# placa_nano.net
KiCad netlist of a schematic drawn in EAGLE
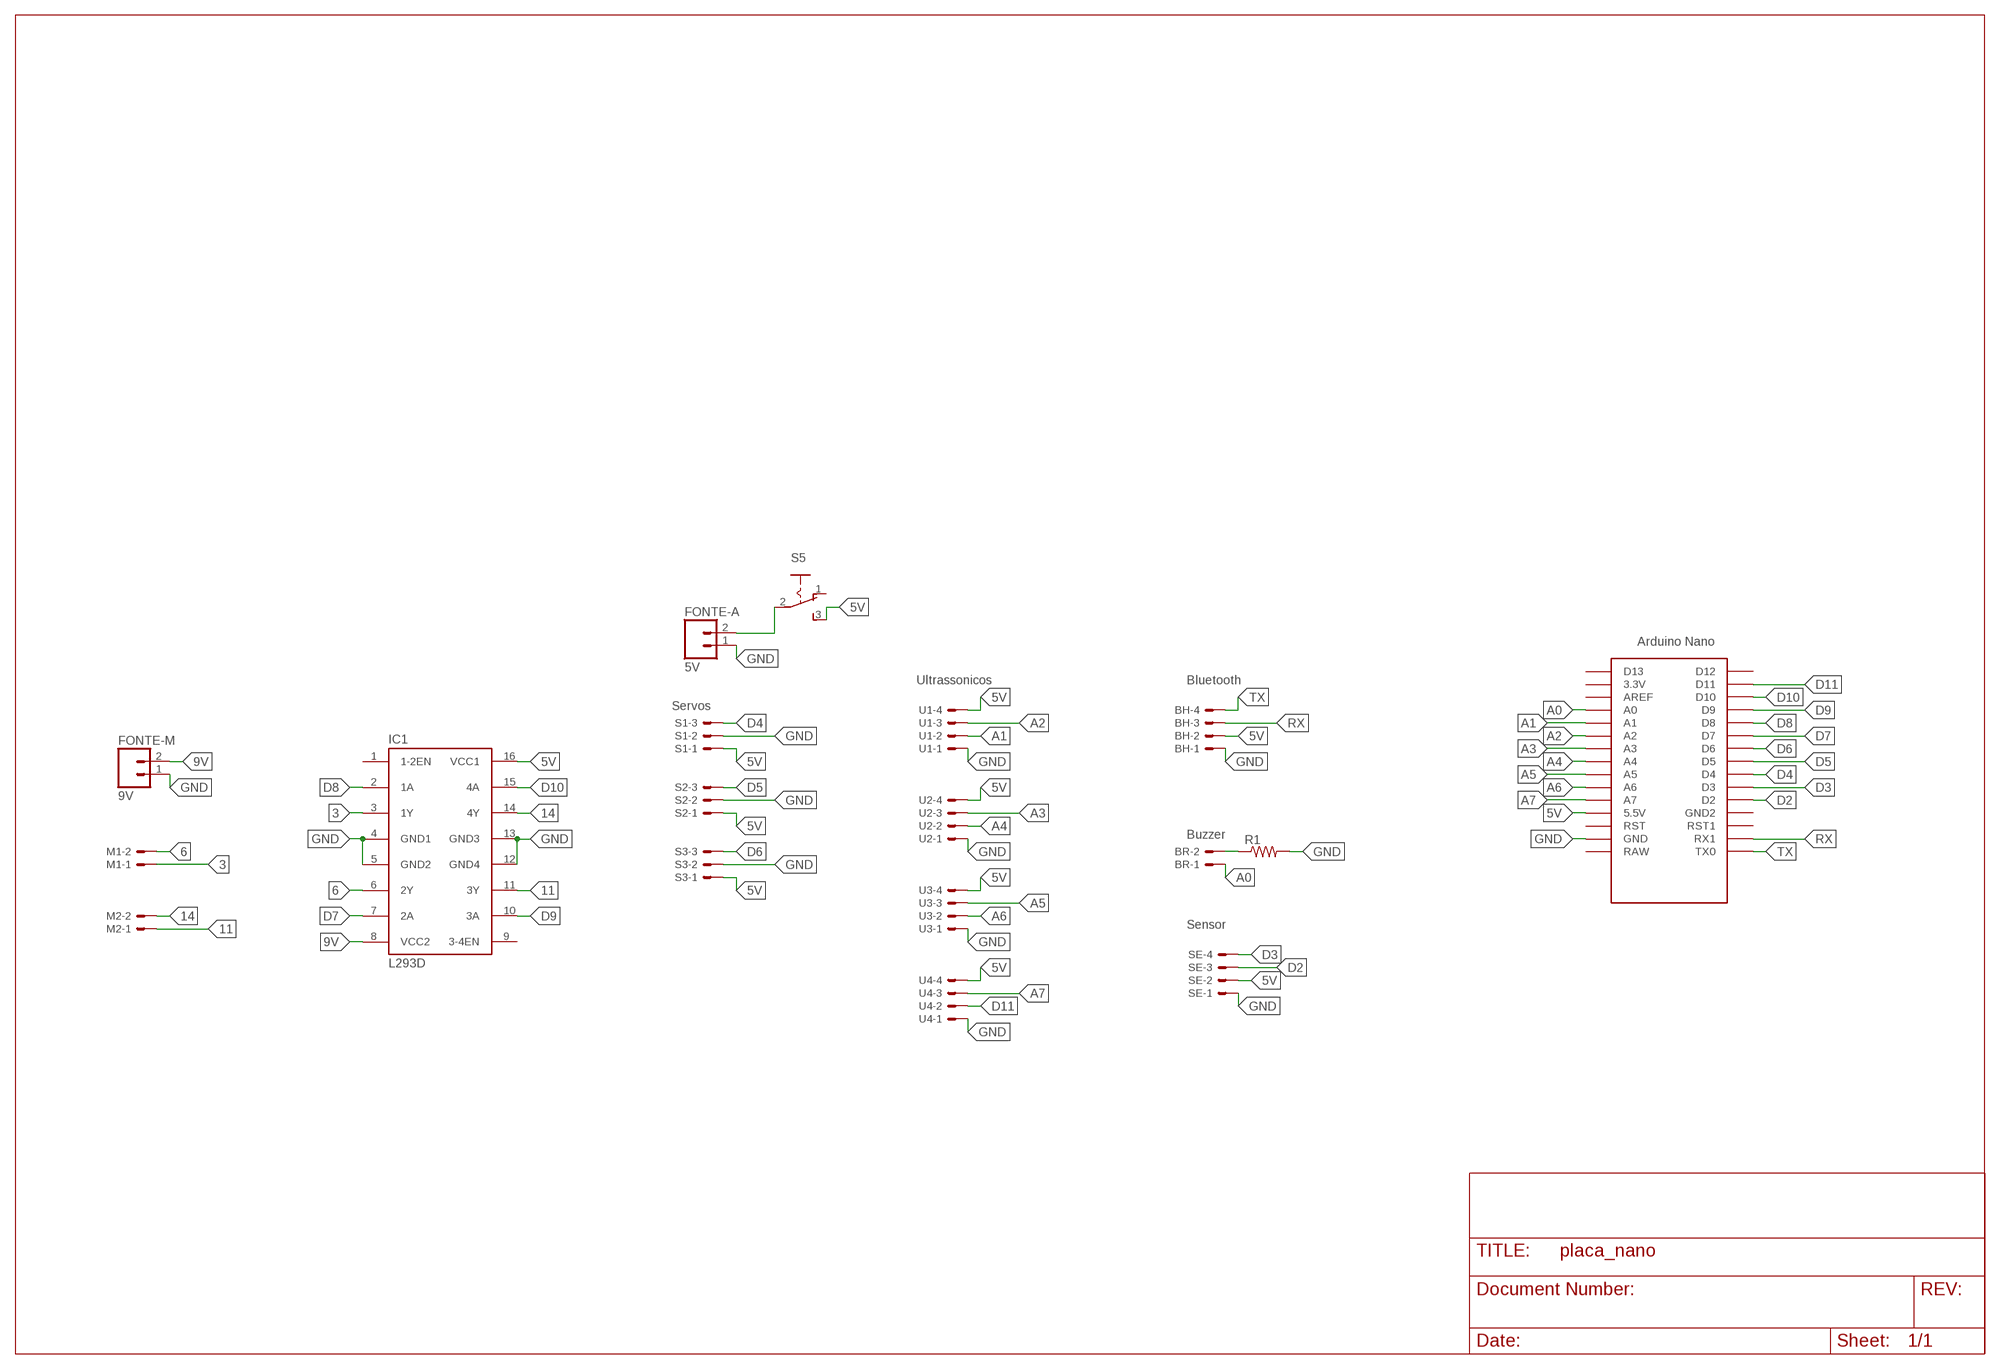
[diagram p0: schematic, sheet 1]

(export (version "E")
  (design (tool "Eeschema 10.0.6"))
  (components
    (comp (ref "BH")
      (value "22-23-2041")
      (footprint "eagle-import:22-23-2041")
      (fields (field (name "MF") "MOLEX"))
      (libsource (lib "eagle-import") (part "22-23-2041"))
    )
    (comp (ref "BR")
      (value "22-23-2021")
      (footprint "eagle-import:22-23-2021")
      (fields (field (name "MF") "MOLEX"))
      (libsource (lib "eagle-import") (part "22-23-2021"))
    )
    (comp (ref "FONTE-A")
      (value "5V")
      (footprint "eagle-import:02P")
      (libsource (lib "eagle-import") (part "M02"))
    )
    (comp (ref "FONTE-M")
      (value "9V")
      (footprint "eagle-import:02P")
      (libsource (lib "eagle-import") (part "M02"))
    )
    (comp (ref "IC1")
      (value "L293D")
      (footprint "eagle-import:DIL16")
      (libsource (lib "eagle-import") (part "L293D"))
    )
    (comp (ref "M1")
      (value "22-23-2021")
      (footprint "eagle-import:22-23-2021")
      (fields (field (name "MF") "MOLEX"))
      (libsource (lib "eagle-import") (part "22-23-2021"))
    )
    (comp (ref "M2")
      (value "22-23-2021")
      (footprint "eagle-import:22-23-2021")
      (fields (field (name "MF") "MOLEX"))
      (libsource (lib "eagle-import") (part "22-23-2021"))
    )
    (comp (ref "R1")
      (value "R-US_0207/10")
      (footprint "eagle-import:0207_10")
      (libsource (lib "eagle-import") (part "R-US_0207/10"))
    )
    (comp (ref "S1")
      (value "22-23-2031")
      (footprint "eagle-import:22-23-2031")
      (fields (field (name "MF") "MOLEX"))
      (libsource (lib "eagle-import") (part "22-23-2031"))
    )
    (comp (ref "S2")
      (value "22-23-2031")
      (footprint "eagle-import:22-23-2031")
      (fields (field (name "MF") "MOLEX"))
      (libsource (lib "eagle-import") (part "22-23-2031"))
    )
    (comp (ref "S3")
      (value "22-23-2031")
      (footprint "eagle-import:22-23-2031")
      (fields (field (name "MF") "MOLEX"))
      (libsource (lib "eagle-import") (part "22-23-2031"))
    )
    (comp (ref "S5")
      (value "255SB")
      (footprint "eagle-import:255SB")
      (libsource (lib "eagle-import") (part "255SB"))
    )
    (comp (ref "SE")
      (value "22-23-2041")
      (footprint "eagle-import:22-23-2041")
      (fields (field (name "MF") "MOLEX"))
      (libsource (lib "eagle-import") (part "22-23-2041"))
    )
    (comp (ref "U$1")
      (value "NANO")
      (footprint "eagle-import:NANO")
      (libsource (lib "eagle-import") (part "NANO"))
    )
    (comp (ref "U1")
      (value "22-23-2041")
      (footprint "eagle-import:22-23-2041")
      (fields (field (name "MF") "MOLEX"))
      (libsource (lib "eagle-import") (part "22-23-2041"))
    )
    (comp (ref "U2")
      (value "22-23-2041")
      (footprint "eagle-import:22-23-2041")
      (fields (field (name "MF") "MOLEX"))
      (libsource (lib "eagle-import") (part "22-23-2041"))
    )
    (comp (ref "U3")
      (value "22-23-2041")
      (footprint "eagle-import:22-23-2041")
      (fields (field (name "MF") "MOLEX"))
      (libsource (lib "eagle-import") (part "22-23-2041"))
    )
    (comp (ref "U4")
      (value "22-23-2041")
      (footprint "eagle-import:22-23-2041")
      (fields (field (name "MF") "MOLEX"))
      (libsource (lib "eagle-import") (part "22-23-2041"))
    )
  )
  (nets
    (net (code "1") (name "3") (class "Default")
      (node (ref "IC1") (pin "3") (pinfunction "1Y_3") (pintype "output"))
      (node (ref "M1") (pin "1") (pinfunction "S_1") (pintype "passive"))
    )
    (net (code "2") (name "5V") (class "Default")
      (node (ref "BH") (pin "2") (pinfunction "S_2") (pintype "passive"))
      (node (ref "FONTE-A") (pin "2") (pinfunction "2_2") (pintype "passive"))
      (node (ref "IC1") (pin "16") (pinfunction "VCC1_16") (pintype "power_in"))
      (node (ref "S1") (pin "1") (pinfunction "S_1") (pintype "passive"))
      (node (ref "S2") (pin "1") (pinfunction "S_1") (pintype "passive"))
      (node (ref "S3") (pin "1") (pinfunction "S_1") (pintype "passive"))
      (node (ref "S5") (pin "2") (pinfunction "P_2") (pintype "passive"))
      (node (ref "S5") (pin "3") (pinfunction "S_3") (pintype "passive"))
      (node (ref "SE") (pin "2") (pinfunction "S_2") (pintype "passive"))
      (node (ref "U$1") (pin "5V") (pinfunction "5.5V_5V") (pintype "bidirectional"))
      (node (ref "U1") (pin "4") (pinfunction "S_4") (pintype "passive"))
      (node (ref "U2") (pin "4") (pinfunction "S_4") (pintype "passive"))
      (node (ref "U3") (pin "4") (pinfunction "S_4") (pintype "passive"))
      (node (ref "U4") (pin "4") (pinfunction "S_4") (pintype "passive"))
    )
    (net (code "3") (name "6") (class "Default")
      (node (ref "IC1") (pin "6") (pinfunction "2Y_6") (pintype "output"))
      (node (ref "M1") (pin "2") (pinfunction "S_2") (pintype "passive"))
    )
    (net (code "4") (name "9V") (class "Default")
      (node (ref "FONTE-M") (pin "2") (pinfunction "2_2") (pintype "passive"))
      (node (ref "IC1") (pin "8") (pinfunction "VCC2_8") (pintype "power_in"))
    )
    (net (code "5") (name "11") (class "Default")
      (node (ref "IC1") (pin "11") (pinfunction "3Y_11") (pintype "output"))
      (node (ref "M2") (pin "1") (pinfunction "S_1") (pintype "passive"))
    )
    (net (code "6") (name "14") (class "Default")
      (node (ref "IC1") (pin "14") (pinfunction "4Y_14") (pintype "output"))
      (node (ref "M2") (pin "2") (pinfunction "S_2") (pintype "passive"))
    )
    (net (code "7") (name "A0") (class "Default")
      (node (ref "BR") (pin "1") (pinfunction "S_1") (pintype "passive"))
      (node (ref "U$1") (pin "A0") (pinfunction "A0_A0") (pintype "bidirectional"))
    )
    (net (code "8") (name "A1") (class "Default")
      (node (ref "U$1") (pin "A1") (pinfunction "A1_A1") (pintype "bidirectional"))
      (node (ref "U1") (pin "2") (pinfunction "S_2") (pintype "passive"))
    )
    (net (code "9") (name "A2") (class "Default")
      (node (ref "U$1") (pin "A2") (pinfunction "A2_A2") (pintype "bidirectional"))
      (node (ref "U1") (pin "3") (pinfunction "S_3") (pintype "passive"))
    )
    (net (code "10") (name "A3") (class "Default")
      (node (ref "U$1") (pin "A3") (pinfunction "A3_A3") (pintype "bidirectional"))
      (node (ref "U2") (pin "3") (pinfunction "S_3") (pintype "passive"))
    )
    (net (code "11") (name "A4") (class "Default")
      (node (ref "U$1") (pin "A4") (pinfunction "A4_A4") (pintype "bidirectional"))
      (node (ref "U2") (pin "2") (pinfunction "S_2") (pintype "passive"))
    )
    (net (code "12") (name "A5") (class "Default")
      (node (ref "U$1") (pin "A5") (pinfunction "A5_A5") (pintype "bidirectional"))
      (node (ref "U3") (pin "3") (pinfunction "S_3") (pintype "passive"))
    )
    (net (code "13") (name "A6") (class "Default")
      (node (ref "U$1") (pin "A6") (pinfunction "A6_A6") (pintype "bidirectional"))
      (node (ref "U3") (pin "2") (pinfunction "S_2") (pintype "passive"))
    )
    (net (code "14") (name "A7") (class "Default")
      (node (ref "U$1") (pin "A7") (pinfunction "A7_A7") (pintype "bidirectional"))
      (node (ref "U4") (pin "3") (pinfunction "S_3") (pintype "passive"))
    )
    (net (code "15") (name "D2") (class "Default")
      (node (ref "SE") (pin "3") (pinfunction "S_3") (pintype "passive"))
      (node (ref "U$1") (pin "D2") (pinfunction "D2_D2") (pintype "bidirectional"))
    )
    (net (code "16") (name "D3") (class "Default")
      (node (ref "SE") (pin "4") (pinfunction "S_4") (pintype "passive"))
      (node (ref "U$1") (pin "D3") (pinfunction "D3_D3") (pintype "bidirectional"))
    )
    (net (code "17") (name "D4") (class "Default")
      (node (ref "S1") (pin "3") (pinfunction "S_3") (pintype "passive"))
      (node (ref "U$1") (pin "D4") (pinfunction "D4_D4") (pintype "bidirectional"))
    )
    (net (code "18") (name "D5") (class "Default")
      (node (ref "S2") (pin "3") (pinfunction "S_3") (pintype "passive"))
      (node (ref "U$1") (pin "D5") (pinfunction "D5_D5") (pintype "bidirectional"))
    )
    (net (code "19") (name "D6") (class "Default")
      (node (ref "S3") (pin "3") (pinfunction "S_3") (pintype "passive"))
      (node (ref "U$1") (pin "D6") (pinfunction "D6_D6") (pintype "bidirectional"))
    )
    (net (code "20") (name "D7") (class "Default")
      (node (ref "IC1") (pin "7") (pinfunction "2A_7") (pintype "input"))
      (node (ref "U$1") (pin "D7") (pinfunction "D7_D7") (pintype "bidirectional"))
    )
    (net (code "21") (name "D8") (class "Default")
      (node (ref "IC1") (pin "2") (pinfunction "1A_2") (pintype "input"))
      (node (ref "U$1") (pin "D8") (pinfunction "D8_D8") (pintype "bidirectional"))
    )
    (net (code "22") (name "D9") (class "Default")
      (node (ref "IC1") (pin "10") (pinfunction "3A_10") (pintype "input"))
      (node (ref "U$1") (pin "D9") (pinfunction "D9_D9") (pintype "bidirectional"))
    )
    (net (code "23") (name "D10") (class "Default")
      (node (ref "IC1") (pin "15") (pinfunction "4A_15") (pintype "input"))
      (node (ref "U$1") (pin "D10") (pinfunction "D10_D10") (pintype "bidirectional"))
    )
    (net (code "24") (name "D11") (class "Default")
      (node (ref "U$1") (pin "D11") (pinfunction "D11_D11") (pintype "bidirectional"))
      (node (ref "U4") (pin "2") (pinfunction "S_2") (pintype "passive"))
    )
    (net (code "25") (name "GND") (class "Default")
      (node (ref "BH") (pin "1") (pinfunction "S_1") (pintype "passive"))
      (node (ref "FONTE-A") (pin "1") (pinfunction "1_1") (pintype "passive"))
      (node (ref "FONTE-M") (pin "1") (pinfunction "1_1") (pintype "passive"))
      (node (ref "IC1") (pin "12") (pinfunction "GND4_12") (pintype "power_in"))
      (node (ref "IC1") (pin "13") (pinfunction "GND3_13") (pintype "power_in"))
      (node (ref "IC1") (pin "4") (pinfunction "GND1_4") (pintype "power_in"))
      (node (ref "IC1") (pin "5") (pinfunction "GND2_5") (pintype "power_in"))
      (node (ref "R1") (pin "2") (pinfunction "2_2") (pintype "passive"))
      (node (ref "S1") (pin "2") (pinfunction "S_2") (pintype "passive"))
      (node (ref "S2") (pin "2") (pinfunction "S_2") (pintype "passive"))
      (node (ref "S3") (pin "2") (pinfunction "S_2") (pintype "passive"))
      (node (ref "SE") (pin "1") (pinfunction "S_1") (pintype "passive"))
      (node (ref "U$1") (pin "GND") (pinfunction "GND_GND") (pintype "bidirectional"))
      (node (ref "U1") (pin "1") (pinfunction "S_1") (pintype "passive"))
      (node (ref "U2") (pin "1") (pinfunction "S_1") (pintype "passive"))
      (node (ref "U3") (pin "1") (pinfunction "S_1") (pintype "passive"))
      (node (ref "U4") (pin "1") (pinfunction "S_1") (pintype "passive"))
    )
    (net (code "26") (name "Net-(BRB-S)") (class "Default")
      (node (ref "BR") (pin "2") (pinfunction "S_2") (pintype "passive"))
      (node (ref "R1") (pin "1") (pinfunction "1_1") (pintype "passive"))
    )
    (net (code "27") (name "RX") (class "Default")
      (node (ref "BH") (pin "3") (pinfunction "S_3") (pintype "passive"))
      (node (ref "U$1") (pin "RX1") (pinfunction "RX1_RX1") (pintype "bidirectional"))
    )
    (net (code "28") (name "TX") (class "Default")
      (node (ref "BH") (pin "4") (pinfunction "S_4") (pintype "passive"))
      (node (ref "U$1") (pin "TX0") (pinfunction "TX0_TX0") (pintype "bidirectional"))
    )
    (net (code "29") (name "unconnected-(IC1-1-2EN-Pad1)") (class "Default")
      (node (ref "IC1") (pin "1") (pinfunction "1-2EN_1") (pintype "input"))
    )
    (net (code "30") (name "unconnected-(IC1-3-4EN-Pad9)") (class "Default")
      (node (ref "IC1") (pin "9") (pinfunction "3-4EN_9") (pintype "input"))
    )
    (net (code "31") (name "unconnected-(S5-O-Pad1)") (class "Default")
      (node (ref "S5") (pin "1") (pinfunction "O_1") (pintype "passive"))
    )
    (net (code "32") (name "unconnected-(U$1-GND2-PadGND1)") (class "Default")
      (node (ref "U$1") (pin "GND1") (pinfunction "GND2_GND1") (pintype "bidirectional"))
    )
    (net (code "33") (name "unconnected-(U$1-Pad3.3V)") (class "Default")
      (node (ref "U$1") (pin "3.3V") (pinfunction "3.3V_3.3V") (pintype "bidirectional"))
    )
    (net (code "34") (name "unconnected-(U$1-PadAREF)") (class "Default")
      (node (ref "U$1") (pin "AREF") (pinfunction "AREF_AREF") (pintype "bidirectional"))
    )
    (net (code "35") (name "unconnected-(U$1-PadD12)") (class "Default")
      (node (ref "U$1") (pin "D12") (pinfunction "D12_D12") (pintype "bidirectional"))
    )
    (net (code "36") (name "unconnected-(U$1-PadD13)") (class "Default")
      (node (ref "U$1") (pin "D13") (pinfunction "D13_D13") (pintype "bidirectional"))
    )
    (net (code "37") (name "unconnected-(U$1-PadRAW)") (class "Default")
      (node (ref "U$1") (pin "RAW") (pinfunction "RAW_RAW") (pintype "bidirectional"))
    )
    (net (code "38") (name "unconnected-(U$1-PadRST)") (class "Default")
      (node (ref "U$1") (pin "RST") (pinfunction "RST_RST") (pintype "bidirectional"))
    )
    (net (code "39") (name "unconnected-(U$1-PadRST1)") (class "Default")
      (node (ref "U$1") (pin "RST1") (pinfunction "RST1_RST1") (pintype "bidirectional"))
    )
  )
)
